# hamilton.net
KiCad netlist of a schematic drawn in EAGLE
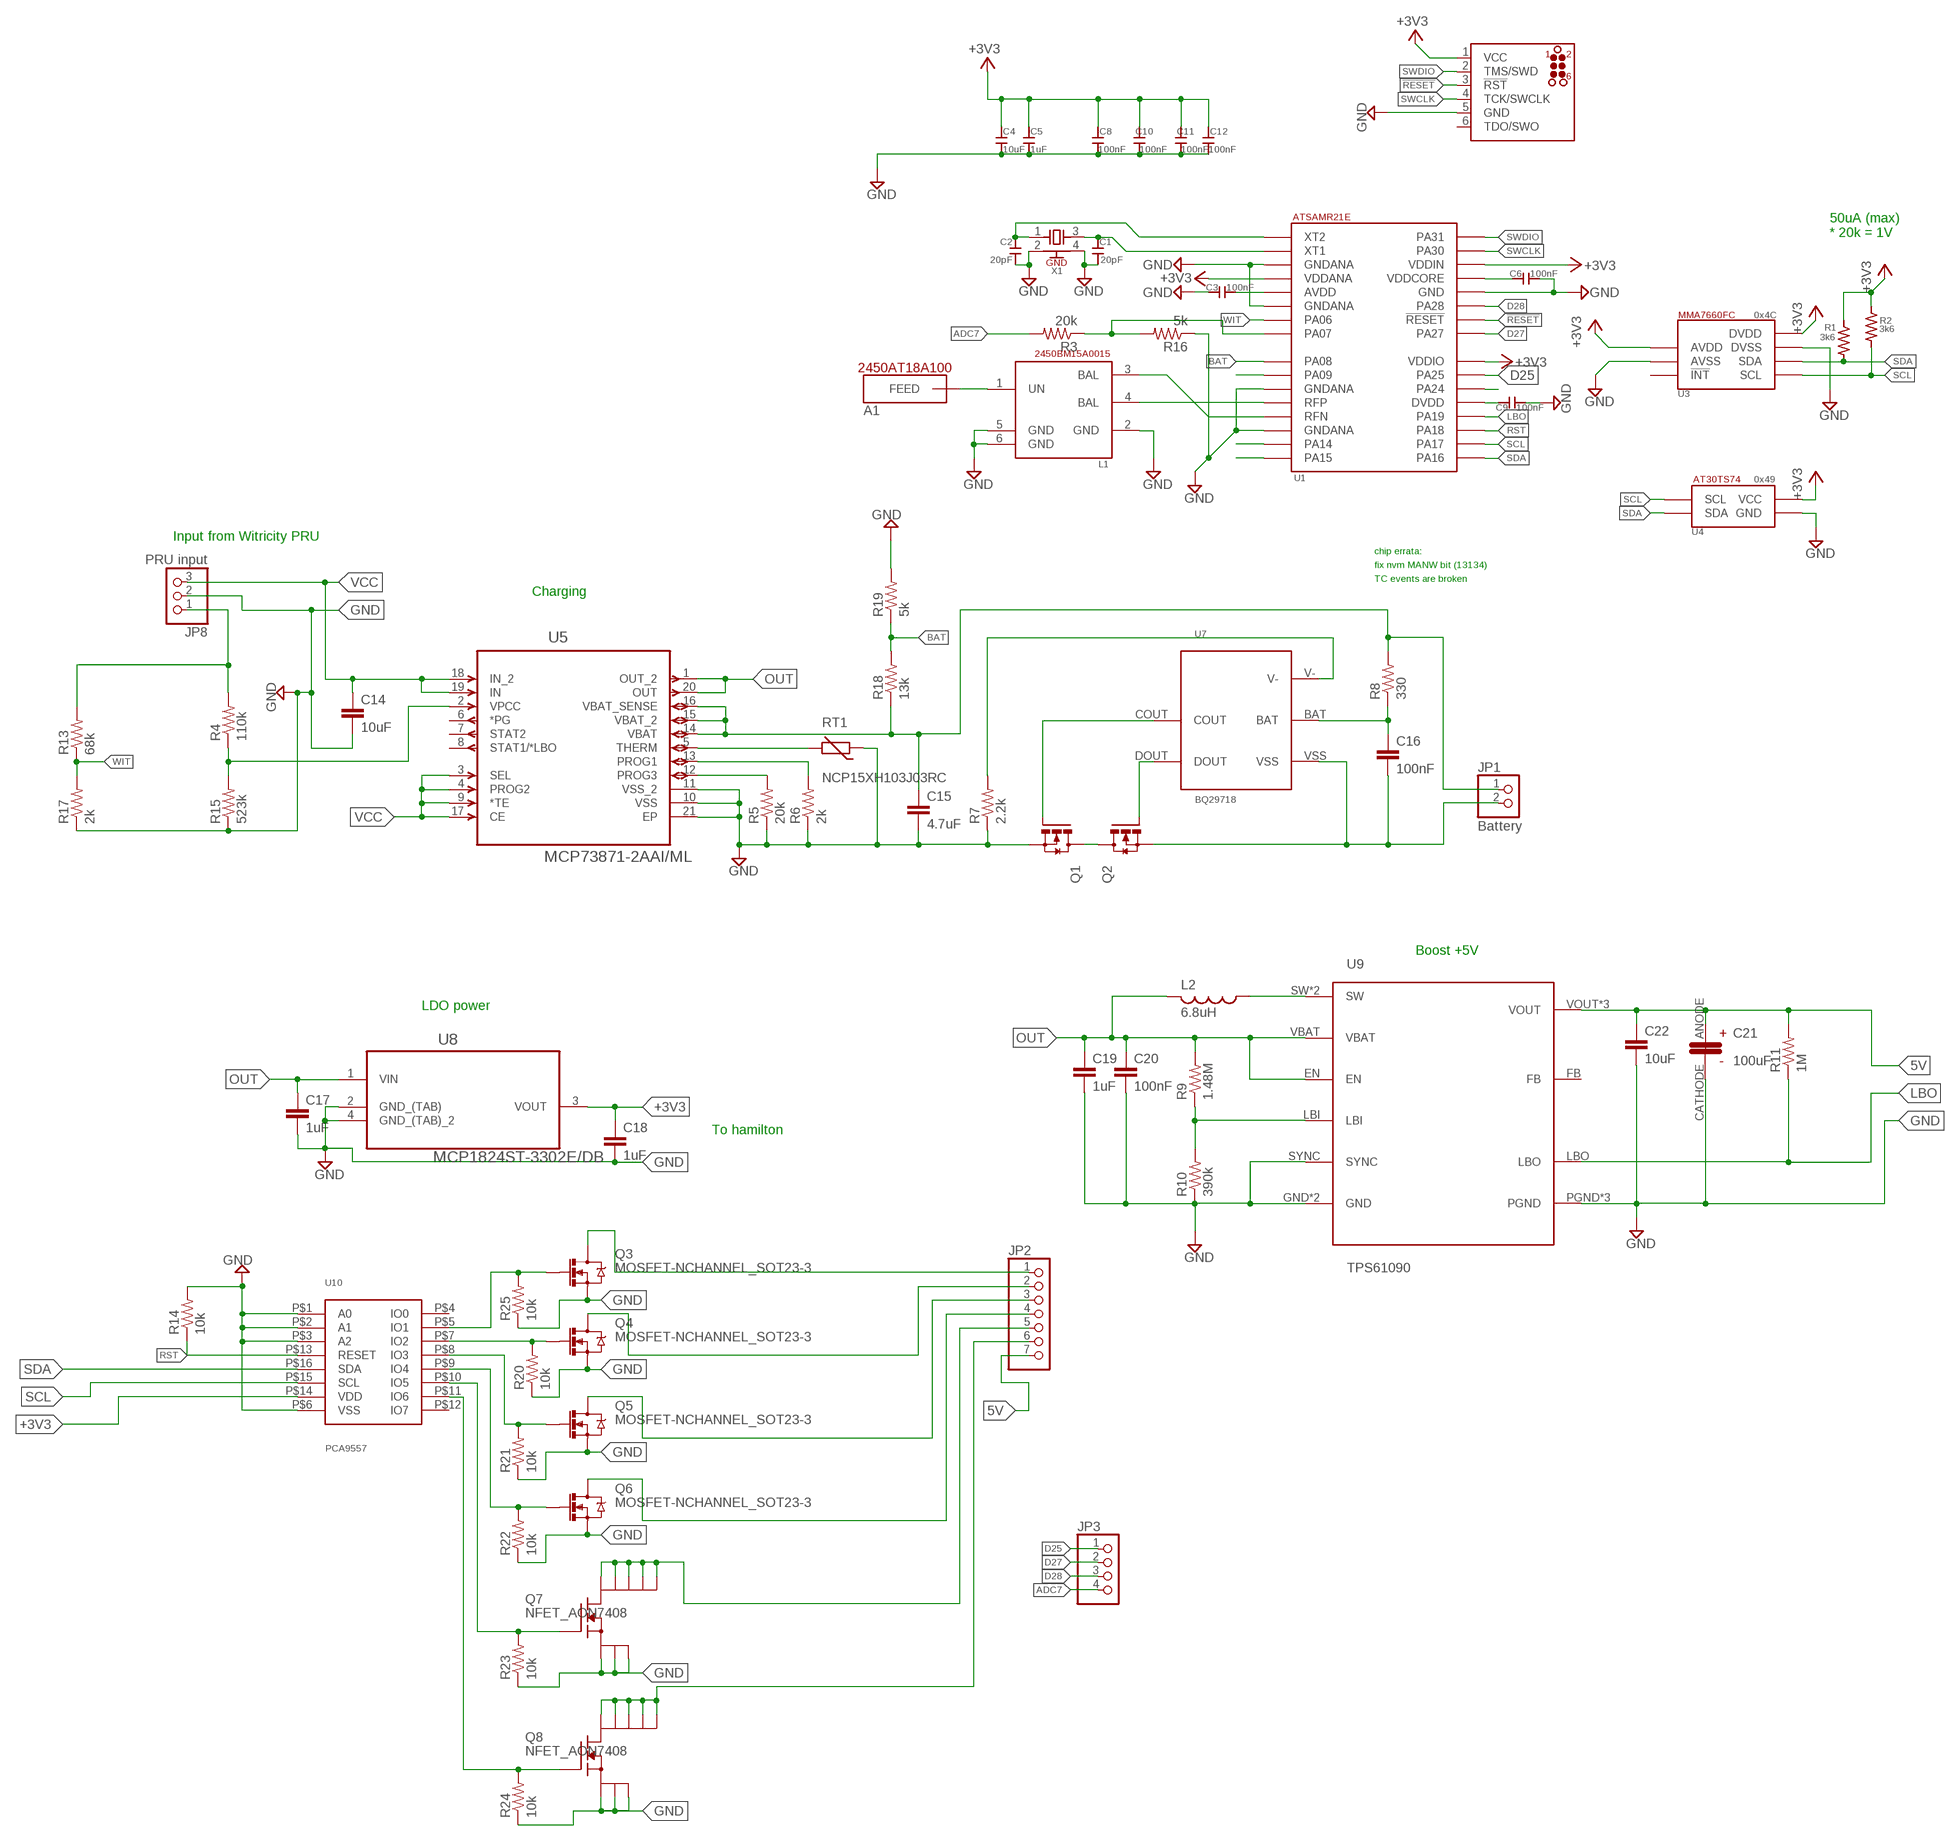
[diagram p0: schematic, sheet 1]

(export (version "E")
  (design (tool "Eeschema 10.0.6"))
  (components
    (comp (ref "A1")
      (value "JOHANSON_ANTENNA2")
      (footprint "eagle-import:JOHANSON_ANTENNA2")
      (libsource (lib "eagle-import") (part "JOHANSON_ANTENNA2"))
    )
    (comp (ref "C1")
      (value "20pF")
      (footprint "eagle-import:S0402")
      (libsource (lib "eagle-import") (part "0603_CAPACITORSMALL"))
    )
    (comp (ref "C2")
      (value "20pF")
      (footprint "eagle-import:S0402")
      (libsource (lib "eagle-import") (part "0603_CAPACITORSMALL"))
    )
    (comp (ref "C3")
      (value "100nF")
      (footprint "eagle-import:C0402")
      (libsource (lib "eagle-import") (part "0603_CAPACITOR0402"))
    )
    (comp (ref "C4")
      (value "10uF")
      (footprint "eagle-import:0805")
      (libsource (lib "eagle-import") (part "0805_CAPACITOR"))
    )
    (comp (ref "C5")
      (value "1uF")
      (footprint "eagle-import:C0402")
      (libsource (lib "eagle-import") (part "0603_CAPACITOR0402"))
    )
    (comp (ref "C6")
      (value "100nF")
      (footprint "eagle-import:C0402")
      (libsource (lib "eagle-import") (part "0603_CAPACITOR0402"))
    )
    (comp (ref "C8")
      (value "100nF")
      (footprint "eagle-import:C0402")
      (libsource (lib "eagle-import") (part "0603_CAPACITOR0402"))
    )
    (comp (ref "C9")
      (value "100nF")
      (footprint "eagle-import:C0402")
      (libsource (lib "eagle-import") (part "0603_CAPACITOR0402"))
    )
    (comp (ref "C10")
      (value "100nF")
      (footprint "eagle-import:C0402")
      (libsource (lib "eagle-import") (part "0603_CAPACITOR0402"))
    )
    (comp (ref "C11")
      (value "100nF")
      (footprint "eagle-import:C0402")
      (libsource (lib "eagle-import") (part "0603_CAPACITOR0402"))
    )
    (comp (ref "C12")
      (value "100nF")
      (footprint "eagle-import:C0402")
      (libsource (lib "eagle-import") (part "0603_CAPACITOR0402"))
    )
    (comp (ref "C14")
      (value "10uF")
      (footprint "eagle-import:C0603")
      (libsource (lib "eagle-import") (part "C-EUC0603"))
    )
    (comp (ref "C15")
      (value "4.7uF")
      (footprint "eagle-import:C0603")
      (libsource (lib "eagle-import") (part "C-EUC0603"))
    )
    (comp (ref "C16")
      (value "100nF")
      (footprint "eagle-import:C0603")
      (libsource (lib "eagle-import") (part "C-EUC0603"))
    )
    (comp (ref "C17")
      (value "1uF")
      (footprint "eagle-import:C0603")
      (libsource (lib "eagle-import") (part "C-EUC0603"))
    )
    (comp (ref "C18")
      (value "1uF")
      (footprint "eagle-import:C0603")
      (libsource (lib "eagle-import") (part "C-EUC0603"))
    )
    (comp (ref "C19")
      (value "1uF")
      (footprint "eagle-import:C0603")
      (libsource (lib "eagle-import") (part "C-EUC0603"))
    )
    (comp (ref "C20")
      (value "100nF")
      (footprint "eagle-import:C0603")
      (libsource (lib "eagle-import") (part "C-EUC0603"))
    )
    (comp (ref "C21")
      (value "100uF")
      (footprint "eagle-import:6032")
      (libsource (lib "eagle-import") (part "T491C686K010AT"))
    )
    (comp (ref "C22")
      (value "10uF")
      (footprint "eagle-import:C0603")
      (libsource (lib "eagle-import") (part "C-EUC0603"))
    )
    (comp (ref "JP1")
      (value "Battery")
      (footprint "eagle-import:1X02")
      (libsource (lib "eagle-import") (part "PINHD-1X2"))
    )
    (comp (ref "JP2")
      (value "PINHD-1X7")
      (footprint "eagle-import:1X07")
      (libsource (lib "eagle-import") (part "PINHD-1X7"))
    )
    (comp (ref "JP3")
      (value "PINHD-1X4")
      (footprint "eagle-import:1X04")
      (libsource (lib "eagle-import") (part "PINHD-1X4"))
    )
    (comp (ref "JP8")
      (value "PRU input")
      (footprint "eagle-import:1X03")
      (libsource (lib "eagle-import") (part "PINHD-1X3"))
    )
    (comp (ref "L1")
      (value "BALUN_JOHANSON")
      (footprint "eagle-import:BALUN_JOHANSON")
      (libsource (lib "eagle-import") (part "BALUN_JOHANSON"))
    )
    (comp (ref "L2")
      (value "6.8uH")
      (footprint "eagle-import:2-SMD-7.8-7-5")
      (libsource (lib "eagle-import") (part "L-744787068"))
    )
    (comp (ref "Q1")
      (value "CSD16301Q2")
      (footprint "eagle-import:6-SMD")
      (libsource (lib "eagle-import") (part "CSD16301Q2"))
    )
    (comp (ref "Q2")
      (value "CSD16301Q2")
      (footprint "eagle-import:6-SMD")
      (libsource (lib "eagle-import") (part "CSD16301Q2"))
    )
    (comp (ref "Q3")
      (value "MOSFET-NCHANNEL_SOT23-3")
      (footprint "eagle-import:SOT23-3")
      (libsource (lib "eagle-import") (part "MOSFET-NCHANNEL_SOT23-3"))
    )
    (comp (ref "Q4")
      (value "MOSFET-NCHANNEL_SOT23-3")
      (footprint "eagle-import:SOT23-3")
      (libsource (lib "eagle-import") (part "MOSFET-NCHANNEL_SOT23-3"))
    )
    (comp (ref "Q5")
      (value "MOSFET-NCHANNEL_SOT23-3")
      (footprint "eagle-import:SOT23-3")
      (libsource (lib "eagle-import") (part "MOSFET-NCHANNEL_SOT23-3"))
    )
    (comp (ref "Q6")
      (value "MOSFET-NCHANNEL_SOT23-3")
      (footprint "eagle-import:SOT23-3")
      (libsource (lib "eagle-import") (part "MOSFET-NCHANNEL_SOT23-3"))
    )
    (comp (ref "Q7")
      (value "NFET_AON7408")
      (footprint "eagle-import:VDFN3X38L")
      (libsource (lib "eagle-import") (part "NFET_AON7408"))
    )
    (comp (ref "Q8")
      (value "NFET_AON7408")
      (footprint "eagle-import:VDFN3X38L")
      (libsource (lib "eagle-import") (part "NFET_AON7408"))
    )
    (comp (ref "R1")
      (value "3k6")
      (footprint "eagle-import:S0402")
      (libsource (lib "eagle-import") (part "0603_RESISTORSMALL"))
    )
    (comp (ref "R2")
      (value "3k6")
      (footprint "eagle-import:S0402")
      (libsource (lib "eagle-import") (part "0603_RESISTORSMALL"))
    )
    (comp (ref "R3")
      (value "20k")
      (footprint "eagle-import:R0402")
      (libsource (lib "eagle-import") (part "R-US_R0402"))
    )
    (comp (ref "R4")
      (value "110k")
      (footprint "eagle-import:R0603")
      (libsource (lib "eagle-import") (part "R-US_R0603"))
    )
    (comp (ref "R5")
      (value "20k")
      (footprint "eagle-import:R0603")
      (libsource (lib "eagle-import") (part "R-US_R0603"))
    )
    (comp (ref "R6")
      (value "2k")
      (footprint "eagle-import:R0603")
      (libsource (lib "eagle-import") (part "R-US_R0603"))
    )
    (comp (ref "R7")
      (value "2.2k")
      (footprint "eagle-import:R0603")
      (libsource (lib "eagle-import") (part "R-US_R0603"))
    )
    (comp (ref "R8")
      (value "330")
      (footprint "eagle-import:R0603")
      (libsource (lib "eagle-import") (part "R-US_R0603"))
    )
    (comp (ref "R9")
      (value "1.48M")
      (footprint "eagle-import:R0603")
      (libsource (lib "eagle-import") (part "R-US_R0603"))
    )
    (comp (ref "R10")
      (value "390k")
      (footprint "eagle-import:R0603")
      (libsource (lib "eagle-import") (part "R-US_R0603"))
    )
    (comp (ref "R11")
      (value "1M")
      (footprint "eagle-import:R0603")
      (libsource (lib "eagle-import") (part "R-US_R0603"))
    )
    (comp (ref "R13")
      (value "68k")
      (footprint "eagle-import:R0402")
      (libsource (lib "eagle-import") (part "R-US_R0402"))
    )
    (comp (ref "R14")
      (value "10k")
      (footprint "eagle-import:R0603")
      (libsource (lib "eagle-import") (part "R-US_R0603"))
    )
    (comp (ref "R15")
      (value "523k")
      (footprint "eagle-import:R0603")
      (libsource (lib "eagle-import") (part "R-US_R0603"))
    )
    (comp (ref "R16")
      (value "5k")
      (footprint "eagle-import:R0402")
      (libsource (lib "eagle-import") (part "R-US_R0402"))
    )
    (comp (ref "R17")
      (value "2k")
      (footprint "eagle-import:R0402")
      (libsource (lib "eagle-import") (part "R-US_R0402"))
    )
    (comp (ref "R18")
      (value "13k")
      (footprint "eagle-import:R0402")
      (libsource (lib "eagle-import") (part "R-US_R0402"))
    )
    (comp (ref "R19")
      (value "5k")
      (footprint "eagle-import:R0402")
      (libsource (lib "eagle-import") (part "R-US_R0402"))
    )
    (comp (ref "R20")
      (value "10k")
      (footprint "eagle-import:R0402")
      (libsource (lib "eagle-import") (part "R-US_R0402"))
    )
    (comp (ref "R21")
      (value "10k")
      (footprint "eagle-import:R0402")
      (libsource (lib "eagle-import") (part "R-US_R0402"))
    )
    (comp (ref "R22")
      (value "10k")
      (footprint "eagle-import:R0402")
      (libsource (lib "eagle-import") (part "R-US_R0402"))
    )
    (comp (ref "R23")
      (value "10k")
      (footprint "eagle-import:R0402")
      (libsource (lib "eagle-import") (part "R-US_R0402"))
    )
    (comp (ref "R24")
      (value "10k")
      (footprint "eagle-import:R0402")
      (libsource (lib "eagle-import") (part "R-US_R0402"))
    )
    (comp (ref "R25")
      (value "10k")
      (footprint "eagle-import:R0402")
      (libsource (lib "eagle-import") (part "R-US_R0402"))
    )
    (comp (ref "RT1")
      (value "NCP15XH103J03RC")
      (footprint "eagle-import:CT_CN0402")
      (libsource (lib "eagle-import") (part "NCP15XH103J03RC"))
    )
    (comp (ref "U$1")
      (value "JLINK_CONNECT")
      (footprint "eagle-import:TC2030-MCP-NL")
      (libsource (lib "eagle-import") (part "JLINK_CONNECT"))
    )
    (comp (ref "U1")
      (value "SAMR21")
      (footprint "eagle-import:QFN32")
      (libsource (lib "eagle-import") (part "SAMR21"))
    )
    (comp (ref "U3")
      (value "MMA7660FC")
      (footprint "eagle-import:MMA7660")
      (libsource (lib "eagle-import") (part "MMA7660FC"))
    )
    (comp (ref "U4")
      (value "AT30TS74")
      (footprint "eagle-import:4WLCSP")
      (libsource (lib "eagle-import") (part "AT30TS74"))
    )
    (comp (ref "U5")
      (value "MCP73871-2AAI/ML")
      (footprint "eagle-import:QFN50P400X400X100-21N")
      (libsource (lib "eagle-import") (part "MCP73871-2AAI/ML"))
    )
    (comp (ref "U7")
      (value "BQ29718")
      (footprint "eagle-import:6-WFDFN")
      (libsource (lib "eagle-import") (part "BQ29718"))
    )
    (comp (ref "U8")
      (value "MCP1824ST-3302E/DB")
      (footprint "eagle-import:SOT230P700X180-4N")
      (libsource (lib "eagle-import") (part "MCP1824ST-3302E/DB"))
    )
    (comp (ref "U9")
      (value "TPS61090")
      (footprint "eagle-import:QFN-16")
      (libsource (lib "eagle-import") (part "TPS61090"))
    )
    (comp (ref "U10")
      (value "PCA9557")
      (footprint "eagle-import:SOT629-1")
      (libsource (lib "eagle-import") (part "PCA9557"))
    )
    (comp (ref "X1")
      (value "XTAL")
      (footprint "eagle-import:XTAL")
      (libsource (lib "eagle-import") (part "XTAL"))
    )
  )
  (nets
    (net (code "1") (name "+3V3") (class "Default")
      (node (ref "C10") (pin "1") (pinfunction "P$1_1") (pintype "passive"))
      (node (ref "C11") (pin "1") (pinfunction "P$1_1") (pintype "passive"))
      (node (ref "C12") (pin "1") (pinfunction "P$1_1") (pintype "passive"))
      (node (ref "C18") (pin "1") (pinfunction "1_1") (pintype "passive"))
      (node (ref "C4") (pin "2") (pinfunction "P$2_2") (pintype "passive"))
      (node (ref "C5") (pin "2") (pinfunction "P$2_2") (pintype "passive"))
      (node (ref "C8") (pin "1") (pinfunction "P$1_1") (pintype "passive"))
      (node (ref "R1") (pin "P$2") (pinfunction "P$2_P$2") (pintype "passive"))
      (node (ref "R2") (pin "P$2") (pinfunction "P$2_P$2") (pintype "passive"))
      (node (ref "U$1") (pin "1") (pinfunction "VCC_1") (pintype "passive"))
      (node (ref "U1") (pin "24") (pinfunction "VDDIO_24") (pintype "bidirectional"))
      (node (ref "U1") (pin "30") (pinfunction "VDDIN_30") (pintype "bidirectional"))
      (node (ref "U1") (pin "4") (pinfunction "VDDANA_4") (pintype "bidirectional"))
      (node (ref "U10") (pin "P$14") (pinfunction "VDD_P$14") (pintype "bidirectional"))
      (node (ref "U3") (pin "3") (pinfunction "AVDD_3") (pintype "bidirectional"))
      (node (ref "U3") (pin "9") (pinfunction "DVDD_9") (pintype "bidirectional"))
      (node (ref "U4") (pin "A1") (pinfunction "VCC_A1") (pintype "bidirectional"))
      (node (ref "U8") (pin "3") (pinfunction "VOUT_3") (pintype "output"))
    )
    (net (code "2") (name "/~{RESET}") (class "Default")
      (node (ref "U$1") (pin "3") (pinfunction "~{RST}_3") (pintype "bidirectional"))
      (node (ref "U1") (pin "26") (pinfunction "~{RESET}_26") (pintype "bidirectional"))
    )
    (net (code "3") (name "5V") (class "Default")
      (node (ref "C21") (pin "ANODE") (pinfunction "ANODE_ANODE") (pintype "bidirectional"))
      (node (ref "C22") (pin "1") (pinfunction "1_1") (pintype "passive"))
      (node (ref "JP2") (pin "7") (pinfunction "7_7") (pintype "passive"))
      (node (ref "R11") (pin "2") (pinfunction "2_2") (pintype "passive"))
      (node (ref "U9") (pin "VOUT") (pinfunction "VOUT_VOUT") (pintype "bidirectional"))
      (node (ref "U9") (pin "VOUT_2") (pinfunction "VOUT_VOUT_2") (pintype "bidirectional"))
      (node (ref "U9") (pin "VOUT_3") (pinfunction "VOUT_VOUT_3") (pintype "bidirectional"))
    )
    (net (code "4") (name "ADC7") (class "Default")
      (node (ref "JP3") (pin "4") (pinfunction "4_4") (pintype "passive"))
      (node (ref "R3") (pin "2") (pinfunction "2_2") (pintype "passive"))
    )
    (net (code "5") (name "BAT") (class "Default")
      (node (ref "R18") (pin "2") (pinfunction "2_2") (pintype "passive"))
      (node (ref "R19") (pin "1") (pinfunction "1_1") (pintype "passive"))
      (node (ref "U1") (pin "9") (pinfunction "PA08_9") (pintype "bidirectional"))
    )
    (net (code "6") (name "D25") (class "Default")
      (node (ref "JP3") (pin "1") (pinfunction "1_1") (pintype "passive"))
      (node (ref "U1") (pin "23") (pinfunction "PA25_23") (pintype "bidirectional"))
    )
    (net (code "7") (name "D27") (class "Default")
      (node (ref "JP3") (pin "2") (pinfunction "2_2") (pintype "passive"))
      (node (ref "U1") (pin "25") (pinfunction "PA27_25") (pintype "bidirectional"))
    )
    (net (code "8") (name "D28") (class "Default")
      (node (ref "JP3") (pin "3") (pinfunction "3_3") (pintype "passive"))
      (node (ref "U1") (pin "27") (pinfunction "PA28_27") (pintype "bidirectional"))
    )
    (net (code "9") (name "GND") (class "Default")
      (node (ref "C1") (pin "P$1") (pinfunction "P$1_P$1") (pintype "passive"))
      (node (ref "C10") (pin "2") (pinfunction "P$2_2") (pintype "passive"))
      (node (ref "C11") (pin "2") (pinfunction "P$2_2") (pintype "passive"))
      (node (ref "C12") (pin "2") (pinfunction "P$2_2") (pintype "passive"))
      (node (ref "C14") (pin "2") (pinfunction "2_2") (pintype "passive"))
      (node (ref "C15") (pin "2") (pinfunction "2_2") (pintype "passive"))
      (node (ref "C17") (pin "2") (pinfunction "2_2") (pintype "passive"))
      (node (ref "C18") (pin "2") (pinfunction "2_2") (pintype "passive"))
      (node (ref "C19") (pin "2") (pinfunction "2_2") (pintype "passive"))
      (node (ref "C2") (pin "P$1") (pinfunction "P$1_P$1") (pintype "passive"))
      (node (ref "C20") (pin "2") (pinfunction "2_2") (pintype "passive"))
      (node (ref "C21") (pin "CATHODE") (pinfunction "CATHODE_CATHODE") (pintype "bidirectional"))
      (node (ref "C22") (pin "2") (pinfunction "2_2") (pintype "passive"))
      (node (ref "C3") (pin "2") (pinfunction "P$2_2") (pintype "passive"))
      (node (ref "C4") (pin "1") (pinfunction "P$1_1") (pintype "passive"))
      (node (ref "C5") (pin "1") (pinfunction "P$1_1") (pintype "passive"))
      (node (ref "C6") (pin "1") (pinfunction "P$1_1") (pintype "passive"))
      (node (ref "C8") (pin "2") (pinfunction "P$2_2") (pintype "passive"))
      (node (ref "C9") (pin "1") (pinfunction "P$1_1") (pintype "passive"))
      (node (ref "JP8") (pin "2") (pinfunction "2_2") (pintype "passive"))
      (node (ref "L1") (pin "2") (pinfunction "GND_2") (pintype "bidirectional"))
      (node (ref "L1") (pin "5") (pinfunction "GND_5") (pintype "bidirectional"))
      (node (ref "L1") (pin "6") (pinfunction "GND_6") (pintype "bidirectional"))
      (node (ref "Q1") (pin "S_1") (pinfunction "S_S_1") (pintype "passive"))
      (node (ref "Q1") (pin "S_2") (pinfunction "S_S_2") (pintype "passive"))
      (node (ref "Q3") (pin "2") (pinfunction "S_2") (pintype "passive"))
      (node (ref "Q4") (pin "2") (pinfunction "S_2") (pintype "passive"))
      (node (ref "Q5") (pin "2") (pinfunction "S_2") (pintype "passive"))
      (node (ref "Q6") (pin "2") (pinfunction "S_2") (pintype "passive"))
      (node (ref "Q7") (pin "1") (pinfunction "S_1") (pintype "passive"))
      (node (ref "Q7") (pin "2") (pinfunction "S_2") (pintype "bidirectional"))
      (node (ref "Q7") (pin "3") (pinfunction "S_3") (pintype "bidirectional"))
      (node (ref "Q8") (pin "1") (pinfunction "S_1") (pintype "passive"))
      (node (ref "Q8") (pin "2") (pinfunction "S_2") (pintype "bidirectional"))
      (node (ref "Q8") (pin "3") (pinfunction "S_3") (pintype "bidirectional"))
      (node (ref "R10") (pin "1") (pinfunction "1_1") (pintype "passive"))
      (node (ref "R14") (pin "2") (pinfunction "2_2") (pintype "passive"))
      (node (ref "R15") (pin "1") (pinfunction "1_1") (pintype "passive"))
      (node (ref "R16") (pin "1") (pinfunction "1_1") (pintype "passive"))
      (node (ref "R17") (pin "1") (pinfunction "1_1") (pintype "passive"))
      (node (ref "R19") (pin "2") (pinfunction "2_2") (pintype "passive"))
      (node (ref "R20") (pin "1") (pinfunction "1_1") (pintype "passive"))
      (node (ref "R21") (pin "1") (pinfunction "1_1") (pintype "passive"))
      (node (ref "R22") (pin "1") (pinfunction "1_1") (pintype "passive"))
      (node (ref "R23") (pin "1") (pinfunction "1_1") (pintype "passive"))
      (node (ref "R24") (pin "1") (pinfunction "1_1") (pintype "passive"))
      (node (ref "R25") (pin "1") (pinfunction "1_1") (pintype "passive"))
      (node (ref "R5") (pin "1") (pinfunction "1_1") (pintype "passive"))
      (node (ref "R6") (pin "1") (pinfunction "1_1") (pintype "passive"))
      (node (ref "R7") (pin "1") (pinfunction "1_1") (pintype "passive"))
      (node (ref "RT1") (pin "1") (pinfunction "1_1") (pintype "passive"))
      (node (ref "U$1") (pin "5") (pinfunction "GND_5") (pintype "power_in"))
      (node (ref "U1") (pin "11") (pinfunction "GNDANA_11") (pintype "bidirectional"))
      (node (ref "U1") (pin "14") (pinfunction "GNDANA_14") (pintype "bidirectional"))
      (node (ref "U1") (pin "28") (pinfunction "GND_28") (pintype "bidirectional"))
      (node (ref "U1") (pin "3") (pinfunction "GNDANA_3") (pintype "bidirectional"))
      (node (ref "U1") (pin "6") (pinfunction "GNDANA_6") (pintype "bidirectional"))
      (node (ref "U10") (pin "P$1") (pinfunction "A0_P$1") (pintype "bidirectional"))
      (node (ref "U10") (pin "P$2") (pinfunction "A1_P$2") (pintype "bidirectional"))
      (node (ref "U10") (pin "P$3") (pinfunction "A2_P$3") (pintype "bidirectional"))
      (node (ref "U10") (pin "P$6") (pinfunction "VSS_P$6") (pintype "bidirectional"))
      (node (ref "U3") (pin "4") (pinfunction "AVSS_4") (pintype "bidirectional"))
      (node (ref "U3") (pin "8") (pinfunction "DVSS_8") (pintype "bidirectional"))
      (node (ref "U4") (pin "A2") (pinfunction "GND_A2") (pintype "bidirectional"))
      (node (ref "U5") (pin "10") (pinfunction "VSS_10") (pintype "power_in"))
      (node (ref "U5") (pin "11") (pinfunction "VSS_2_11") (pintype "power_in"))
      (node (ref "U5") (pin "21") (pinfunction "EP_21") (pintype "passive"))
      (node (ref "U8") (pin "2") (pinfunction "GND_(TAB)_2") (pintype "passive"))
      (node (ref "U8") (pin "4") (pinfunction "GND_(TAB)_2_4") (pintype "passive"))
      (node (ref "U9") (pin "GND") (pinfunction "GND_GND") (pintype "bidirectional"))
      (node (ref "U9") (pin "P$17") (pinfunction "GND_P$17") (pintype "bidirectional"))
      (node (ref "U9") (pin "PGND") (pinfunction "PGND_PGND") (pintype "bidirectional"))
      (node (ref "U9") (pin "PGND_2") (pinfunction "PGND_PGND_2") (pintype "bidirectional"))
      (node (ref "U9") (pin "PGND_3") (pinfunction "PGND_PGND_3") (pintype "bidirectional"))
      (node (ref "U9") (pin "SYNC") (pinfunction "SYNC_SYNC") (pintype "bidirectional"))
      (node (ref "X1") (pin "2") (pinfunction "GND_2") (pintype "power_in"))
      (node (ref "X1") (pin "4") (pinfunction "GND_4") (pintype "power_in"))
    )
    (net (code "10") (name "LBO") (class "Default")
      (node (ref "R11") (pin "1") (pinfunction "1_1") (pintype "passive"))
      (node (ref "U1") (pin "20") (pinfunction "PA19_20") (pintype "bidirectional"))
      (node (ref "U9") (pin "LBO") (pinfunction "LBO_LBO") (pintype "bidirectional"))
    )
    (net (code "11") (name "Net-(C3-P$1)") (class "Default")
      (node (ref "C3") (pin "1") (pinfunction "P$1_1") (pintype "passive"))
      (node (ref "U1") (pin "5") (pinfunction "AVDD_5") (pintype "bidirectional"))
    )
    (net (code "12") (name "Net-(C6-P$2)") (class "Default")
      (node (ref "C6") (pin "2") (pinfunction "P$2_2") (pintype "passive"))
      (node (ref "U1") (pin "29") (pinfunction "VDDCORE_29") (pintype "bidirectional"))
    )
    (net (code "13") (name "Net-(C9-P$2)") (class "Default")
      (node (ref "C9") (pin "2") (pinfunction "P$2_2") (pintype "passive"))
      (node (ref "U1") (pin "21") (pinfunction "DVDD_21") (pintype "bidirectional"))
    )
    (net (code "14") (name "Net-(C16-Pad1)") (class "Default")
      (node (ref "C16") (pin "1") (pinfunction "1_1") (pintype "passive"))
      (node (ref "R8") (pin "1") (pinfunction "1_1") (pintype "passive"))
      (node (ref "U7") (pin "BAT") (pinfunction "BAT_BAT") (pintype "bidirectional"))
    )
    (net (code "15") (name "Net-(C16-Pad2)") (class "Default")
      (node (ref "C16") (pin "2") (pinfunction "2_2") (pintype "passive"))
      (node (ref "JP1") (pin "2") (pinfunction "2_2") (pintype "passive"))
      (node (ref "Q2") (pin "S_1") (pinfunction "S_S_1") (pintype "passive"))
      (node (ref "Q2") (pin "S_2") (pinfunction "S_S_2") (pintype "passive"))
      (node (ref "U7") (pin "VSS") (pinfunction "VSS_VSS") (pintype "bidirectional"))
    )
    (net (code "16") (name "Net-(JP2-Pad5)") (class "Default")
      (node (ref "JP2") (pin "5") (pinfunction "5_5") (pintype "passive"))
      (node (ref "Q7") (pin "5") (pinfunction "D_5") (pintype "bidirectional"))
      (node (ref "Q7") (pin "6") (pinfunction "D_6") (pintype "bidirectional"))
      (node (ref "Q7") (pin "7") (pinfunction "D_7") (pintype "bidirectional"))
      (node (ref "Q7") (pin "8") (pinfunction "D_8") (pintype "passive"))
      (node (ref "Q7") (pin "PAD") (pinfunction "D_PAD") (pintype "bidirectional"))
    )
    (net (code "17") (name "Net-(JP2-Pad6)") (class "Default")
      (node (ref "JP2") (pin "6") (pinfunction "6_6") (pintype "passive"))
      (node (ref "Q8") (pin "5") (pinfunction "D_5") (pintype "bidirectional"))
      (node (ref "Q8") (pin "6") (pinfunction "D_6") (pintype "bidirectional"))
      (node (ref "Q8") (pin "7") (pinfunction "D_7") (pintype "bidirectional"))
      (node (ref "Q8") (pin "8") (pinfunction "D_8") (pintype "passive"))
      (node (ref "Q8") (pin "PAD") (pinfunction "D_PAD") (pintype "bidirectional"))
    )
    (net (code "18") (name "Net-(JP8-Pad1)") (class "Default")
      (node (ref "JP8") (pin "1") (pinfunction "1_1") (pintype "passive"))
      (node (ref "R13") (pin "2") (pinfunction "2_2") (pintype "passive"))
      (node (ref "R4") (pin "2") (pinfunction "2_2") (pintype "passive"))
    )
    (net (code "19") (name "Net-(L1-UN)") (class "Default")
      (node (ref "A1") (pin "FEED") (pinfunction "FEED_FEED") (pintype "bidirectional"))
      (node (ref "L1") (pin "1") (pinfunction "UN_1") (pintype "bidirectional"))
    )
    (net (code "20") (name "Net-(L2-1)") (class "Default")
      (node (ref "L2") (pin "P$1") (pinfunction "1_P$1") (pintype "passive"))
      (node (ref "U9") (pin "SW") (pinfunction "SW_SW") (pintype "bidirectional"))
      (node (ref "U9") (pin "SW_2") (pinfunction "SW_SW_2") (pintype "bidirectional"))
    )
    (net (code "21") (name "Net-(Q1-D-PadD_1)") (class "Default")
      (node (ref "Q1") (pin "D_1") (pinfunction "D_D_1") (pintype "passive"))
      (node (ref "Q1") (pin "D_2") (pinfunction "D_D_2") (pintype "passive"))
      (node (ref "Q1") (pin "D_3") (pinfunction "D_D_3") (pintype "passive"))
      (node (ref "Q1") (pin "D_4") (pinfunction "D_D_4") (pintype "passive"))
      (node (ref "Q1") (pin "D_5") (pinfunction "D_D_5") (pintype "passive"))
      (node (ref "Q2") (pin "D_1") (pinfunction "D_D_1") (pintype "passive"))
      (node (ref "Q2") (pin "D_2") (pinfunction "D_D_2") (pintype "passive"))
      (node (ref "Q2") (pin "D_3") (pinfunction "D_D_3") (pintype "passive"))
      (node (ref "Q2") (pin "D_4") (pinfunction "D_D_4") (pintype "passive"))
      (node (ref "Q2") (pin "D_5") (pinfunction "D_D_5") (pintype "passive"))
    )
    (net (code "22") (name "Net-(Q1-PadG)") (class "Default")
      (node (ref "Q1") (pin "G") (pinfunction "G_G") (pintype "passive"))
      (node (ref "U7") (pin "COUT") (pinfunction "COUT_COUT") (pintype "bidirectional"))
    )
    (net (code "23") (name "Net-(Q2-PadG)") (class "Default")
      (node (ref "Q2") (pin "G") (pinfunction "G_G") (pintype "passive"))
      (node (ref "U7") (pin "DOUT") (pinfunction "DOUT_DOUT") (pintype "bidirectional"))
    )
    (net (code "24") (name "Net-(Q3-D)") (class "Default")
      (node (ref "JP2") (pin "1") (pinfunction "1_1") (pintype "passive"))
      (node (ref "Q3") (pin "3") (pinfunction "D_3") (pintype "passive"))
    )
    (net (code "25") (name "Net-(Q3-G)") (class "Default")
      (node (ref "Q3") (pin "1") (pinfunction "G_1") (pintype "passive"))
      (node (ref "R25") (pin "2") (pinfunction "2_2") (pintype "passive"))
      (node (ref "U10") (pin "P$5") (pinfunction "IO1_P$5") (pintype "bidirectional"))
    )
    (net (code "26") (name "Net-(Q4-D)") (class "Default")
      (node (ref "JP2") (pin "2") (pinfunction "2_2") (pintype "passive"))
      (node (ref "Q4") (pin "3") (pinfunction "D_3") (pintype "passive"))
    )
    (net (code "27") (name "Net-(Q4-G)") (class "Default")
      (node (ref "Q4") (pin "1") (pinfunction "G_1") (pintype "passive"))
      (node (ref "R20") (pin "2") (pinfunction "2_2") (pintype "passive"))
      (node (ref "U10") (pin "P$7") (pinfunction "IO2_P$7") (pintype "bidirectional"))
    )
    (net (code "28") (name "Net-(Q5-D)") (class "Default")
      (node (ref "JP2") (pin "3") (pinfunction "3_3") (pintype "passive"))
      (node (ref "Q5") (pin "3") (pinfunction "D_3") (pintype "passive"))
    )
    (net (code "29") (name "Net-(Q5-G)") (class "Default")
      (node (ref "Q5") (pin "1") (pinfunction "G_1") (pintype "passive"))
      (node (ref "R21") (pin "2") (pinfunction "2_2") (pintype "passive"))
      (node (ref "U10") (pin "P$8") (pinfunction "IO3_P$8") (pintype "bidirectional"))
    )
    (net (code "30") (name "Net-(Q6-D)") (class "Default")
      (node (ref "JP2") (pin "4") (pinfunction "4_4") (pintype "passive"))
      (node (ref "Q6") (pin "3") (pinfunction "D_3") (pintype "passive"))
    )
    (net (code "31") (name "Net-(Q6-G)") (class "Default")
      (node (ref "Q6") (pin "1") (pinfunction "G_1") (pintype "passive"))
      (node (ref "R22") (pin "2") (pinfunction "2_2") (pintype "passive"))
      (node (ref "U10") (pin "P$9") (pinfunction "IO4_P$9") (pintype "bidirectional"))
    )
    (net (code "32") (name "Net-(Q7-G)") (class "Default")
      (node (ref "Q7") (pin "4") (pinfunction "G_4") (pintype "passive"))
      (node (ref "R23") (pin "2") (pinfunction "2_2") (pintype "passive"))
      (node (ref "U10") (pin "P$10") (pinfunction "IO5_P$10") (pintype "bidirectional"))
    )
    (net (code "33") (name "Net-(Q8-G)") (class "Default")
      (node (ref "Q8") (pin "4") (pinfunction "G_4") (pintype "passive"))
      (node (ref "R24") (pin "2") (pinfunction "2_2") (pintype "passive"))
      (node (ref "U10") (pin "P$11") (pinfunction "IO6_P$11") (pintype "bidirectional"))
    )
    (net (code "34") (name "Net-(R7-Pad2)") (class "Default")
      (node (ref "R7") (pin "2") (pinfunction "2_2") (pintype "passive"))
      (node (ref "U7") (pin "V-") (pinfunction "V-_V-") (pintype "bidirectional"))
    )
    (net (code "35") (name "Net-(R10-Pad2)") (class "Default")
      (node (ref "R10") (pin "2") (pinfunction "2_2") (pintype "passive"))
      (node (ref "R9") (pin "1") (pinfunction "1_1") (pintype "passive"))
      (node (ref "U9") (pin "LBI") (pinfunction "LBI_LBI") (pintype "bidirectional"))
    )
    (net (code "36") (name "Net-(U1-PA07)") (class "Default")
      (node (ref "R16") (pin "2") (pinfunction "2_2") (pintype "passive"))
      (node (ref "R3") (pin "1") (pinfunction "1_1") (pintype "passive"))
      (node (ref "U1") (pin "8") (pinfunction "PA07_8") (pintype "bidirectional"))
    )
    (net (code "37") (name "Net-(U1-RFN)") (class "Default")
      (node (ref "L1") (pin "3") (pinfunction "BAL_3") (pintype "bidirectional"))
      (node (ref "U1") (pin "13") (pinfunction "RFN_13") (pintype "bidirectional"))
    )
    (net (code "38") (name "Net-(U1-RFP)") (class "Default")
      (node (ref "L1") (pin "4") (pinfunction "BAL_4") (pintype "bidirectional"))
      (node (ref "U1") (pin "12") (pinfunction "RFP_12") (pintype "bidirectional"))
    )
    (net (code "39") (name "Net-(U1-XT1)") (class "Default")
      (node (ref "C1") (pin "P$2") (pinfunction "P$2_P$2") (pintype "passive"))
      (node (ref "U1") (pin "2") (pinfunction "XT1_2") (pintype "bidirectional"))
      (node (ref "X1") (pin "3") (pinfunction "X2_3") (pintype "power_in"))
    )
    (net (code "40") (name "Net-(U1-XT2)") (class "Default")
      (node (ref "C2") (pin "P$2") (pinfunction "P$2_P$2") (pintype "passive"))
      (node (ref "U1") (pin "1") (pinfunction "XT2_1") (pintype "bidirectional"))
      (node (ref "X1") (pin "1") (pinfunction "X1_1") (pintype "power_in"))
    )
    (net (code "41") (name "Net-(U5-PROG1)") (class "Default")
      (node (ref "R6") (pin "2") (pinfunction "2_2") (pintype "passive"))
      (node (ref "U5") (pin "13") (pinfunction "PROG1_13") (pintype "bidirectional"))
    )
    (net (code "42") (name "Net-(U5-PROG3)") (class "Default")
      (node (ref "R5") (pin "2") (pinfunction "2_2") (pintype "passive"))
      (node (ref "U5") (pin "12") (pinfunction "PROG3_12") (pintype "bidirectional"))
    )
    (net (code "43") (name "Net-(U5-THERM)") (class "Default")
      (node (ref "RT1") (pin "2") (pinfunction "2_2") (pintype "passive"))
      (node (ref "U5") (pin "5") (pinfunction "THERM_5") (pintype "bidirectional"))
    )
    (net (code "44") (name "Net-(U5-VBAT)") (class "Default")
      (node (ref "C15") (pin "1") (pinfunction "1_1") (pintype "passive"))
      (node (ref "JP1") (pin "1") (pinfunction "1_1") (pintype "passive"))
      (node (ref "R18") (pin "1") (pinfunction "1_1") (pintype "passive"))
      (node (ref "R8") (pin "2") (pinfunction "2_2") (pintype "passive"))
      (node (ref "U5") (pin "14") (pinfunction "VBAT_14") (pintype "bidirectional"))
      (node (ref "U5") (pin "15") (pinfunction "VBAT_2_15") (pintype "bidirectional"))
      (node (ref "U5") (pin "16") (pinfunction "VBAT_SENSE_16") (pintype "bidirectional"))
    )
    (net (code "45") (name "Net-(U5-VPCC)") (class "Default")
      (node (ref "R15") (pin "2") (pinfunction "2_2") (pintype "passive"))
      (node (ref "R4") (pin "1") (pinfunction "1_1") (pintype "passive"))
      (node (ref "U5") (pin "2") (pinfunction "VPCC_2") (pintype "input"))
    )
    (net (code "46") (name "OUT") (class "Default")
      (node (ref "C17") (pin "1") (pinfunction "1_1") (pintype "passive"))
      (node (ref "C19") (pin "1") (pinfunction "1_1") (pintype "passive"))
      (node (ref "C20") (pin "1") (pinfunction "1_1") (pintype "passive"))
      (node (ref "L2") (pin "P$2") (pinfunction "2_P$2") (pintype "passive"))
      (node (ref "R9") (pin "2") (pinfunction "2_2") (pintype "passive"))
      (node (ref "U5") (pin "1") (pinfunction "OUT_2_1") (pintype "output"))
      (node (ref "U5") (pin "20") (pinfunction "OUT_20") (pintype "output"))
      (node (ref "U8") (pin "1") (pinfunction "VIN_1") (pintype "input"))
      (node (ref "U9") (pin "EN") (pinfunction "EN_EN") (pintype "bidirectional"))
      (node (ref "U9") (pin "VBAT") (pinfunction "VBAT_VBAT") (pintype "bidirectional"))
    )
    (net (code "47") (name "RST") (class "Default")
      (node (ref "R14") (pin "1") (pinfunction "1_1") (pintype "passive"))
      (node (ref "U1") (pin "19") (pinfunction "PA18_19") (pintype "bidirectional"))
      (node (ref "U10") (pin "P$13") (pinfunction "RESET_P$13") (pintype "bidirectional"))
    )
    (net (code "48") (name "SCL") (class "Default")
      (node (ref "R2") (pin "P$1") (pinfunction "P$1_P$1") (pintype "passive"))
      (node (ref "U1") (pin "18") (pinfunction "PA17_18") (pintype "bidirectional"))
      (node (ref "U10") (pin "P$15") (pinfunction "SCL_P$15") (pintype "bidirectional"))
      (node (ref "U3") (pin "6") (pinfunction "SCL_6") (pintype "bidirectional"))
      (node (ref "U4") (pin "B2") (pinfunction "SCL_B2") (pintype "bidirectional"))
    )
    (net (code "49") (name "SDA") (class "Default")
      (node (ref "R1") (pin "P$1") (pinfunction "P$1_P$1") (pintype "passive"))
      (node (ref "U1") (pin "17") (pinfunction "PA16_17") (pintype "bidirectional"))
      (node (ref "U10") (pin "P$16") (pinfunction "SDA_P$16") (pintype "bidirectional"))
      (node (ref "U3") (pin "7") (pinfunction "SDA_7") (pintype "bidirectional"))
      (node (ref "U4") (pin "B1") (pinfunction "SDA_B1") (pintype "bidirectional"))
    )
    (net (code "50") (name "SWCLK") (class "Default")
      (node (ref "U$1") (pin "4") (pinfunction "TCK/SWCLK_4") (pintype "bidirectional"))
      (node (ref "U1") (pin "31") (pinfunction "PA30_31") (pintype "bidirectional"))
    )
    (net (code "51") (name "SWDIO") (class "Default")
      (node (ref "U$1") (pin "2") (pinfunction "TMS/SWD_2") (pintype "bidirectional"))
      (node (ref "U1") (pin "32") (pinfunction "PA31_32") (pintype "bidirectional"))
    )
    (net (code "52") (name "VCC") (class "Default")
      (node (ref "C14") (pin "1") (pinfunction "1_1") (pintype "passive"))
      (node (ref "JP8") (pin "3") (pinfunction "3_3") (pintype "passive"))
      (node (ref "U5") (pin "17") (pinfunction "CE_17") (pintype "input"))
      (node (ref "U5") (pin "18") (pinfunction "IN_2_18") (pintype "input"))
      (node (ref "U5") (pin "19") (pinfunction "IN_19") (pintype "input"))
      (node (ref "U5") (pin "3") (pinfunction "SEL_3") (pintype "input"))
      (node (ref "U5") (pin "4") (pinfunction "PROG2_4") (pintype "input"))
      (node (ref "U5") (pin "9") (pinfunction "*TE_9") (pintype "input"))
    )
    (net (code "53") (name "WIT") (class "Default")
      (node (ref "R13") (pin "1") (pinfunction "1_1") (pintype "passive"))
      (node (ref "R17") (pin "2") (pinfunction "2_2") (pintype "passive"))
      (node (ref "U1") (pin "7") (pinfunction "PA06_7") (pintype "bidirectional"))
    )
    (net (code "54") (name "unconnected-(U$1-TDO{slash}SWO-Pad6)") (class "Default")
      (node (ref "U$1") (pin "6") (pinfunction "TDO/SWO_6") (pintype "bidirectional"))
    )
    (net (code "55") (name "unconnected-(U1-PA09-Pad10)") (class "Default")
      (node (ref "U1") (pin "10") (pinfunction "PA09_10") (pintype "bidirectional"))
    )
    (net (code "56") (name "unconnected-(U1-PA14-Pad15)") (class "Default")
      (node (ref "U1") (pin "15") (pinfunction "PA14_15") (pintype "bidirectional"))
    )
    (net (code "57") (name "unconnected-(U1-PA15-Pad16)") (class "Default")
      (node (ref "U1") (pin "16") (pinfunction "PA15_16") (pintype "bidirectional"))
    )
    (net (code "58") (name "unconnected-(U1-PA24-Pad22)") (class "Default")
      (node (ref "U1") (pin "22") (pinfunction "PA24_22") (pintype "bidirectional"))
    )
    (net (code "59") (name "unconnected-(U3-~{INT}-Pad5)") (class "Default")
      (node (ref "U3") (pin "5") (pinfunction "~{INT}_5") (pintype "bidirectional"))
    )
    (net (code "60") (name "unconnected-(U5-*PG-Pad6)") (class "Default")
      (node (ref "U5") (pin "6") (pinfunction "*PG_6") (pintype "output"))
    )
    (net (code "61") (name "unconnected-(U5-STAT1{slash}*LBO-Pad8)") (class "Default")
      (node (ref "U5") (pin "8") (pinfunction "STAT1/*LBO_8") (pintype "output"))
    )
    (net (code "62") (name "unconnected-(U5-STAT2-Pad7)") (class "Default")
      (node (ref "U5") (pin "7") (pinfunction "STAT2_7") (pintype "output"))
    )
    (net (code "63") (name "unconnected-(U9-PadFB)") (class "Default")
      (node (ref "U9") (pin "FB") (pinfunction "FB_FB") (pintype "bidirectional"))
    )
    (net (code "64") (name "unconnected-(U10-IO0-PadP$4)") (class "Default")
      (node (ref "U10") (pin "P$4") (pinfunction "IO0_P$4") (pintype "bidirectional"))
    )
    (net (code "65") (name "unconnected-(U10-IO7-PadP$12)") (class "Default")
      (node (ref "U10") (pin "P$12") (pinfunction "IO7_P$12") (pintype "bidirectional"))
    )
  )
)
